# ESP8266.net
KiCad netlist of a schematic drawn in EAGLE
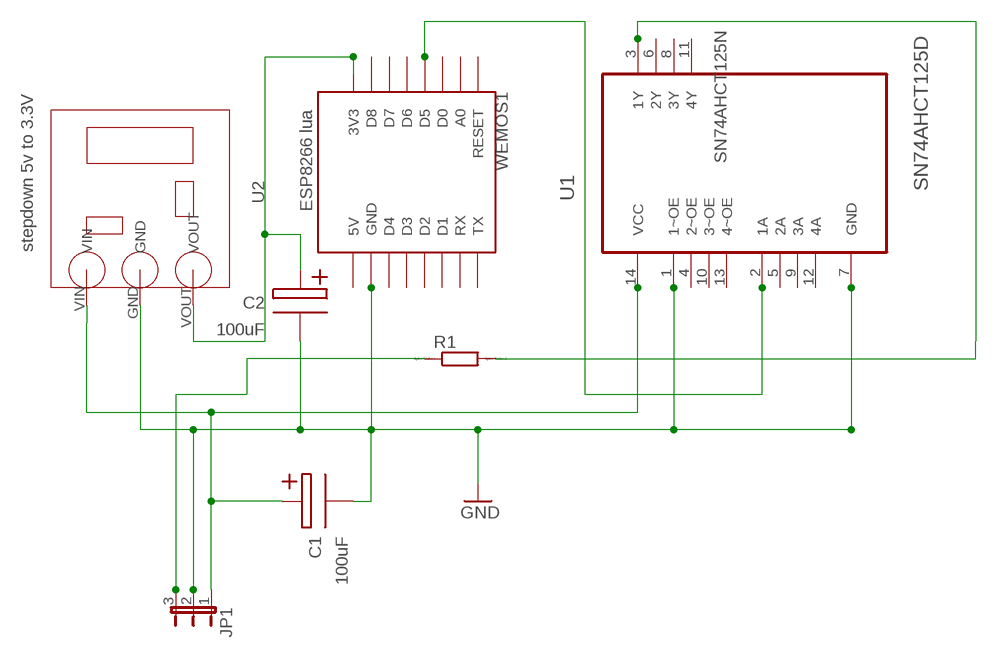
[diagram p0: schematic, sheet 1]

(export (version "E")
  (design (tool "Eeschema 10.0.6"))
  (components
    (comp (ref "C1")
      (value "100uF")
      (footprint "eagle-import:GEPOLTER_ELEKTROLYTKONDENSATOR")
      (libsource (lib "eagle-import") (part "GEPOLTER_ELEKTROLYTKONDENSATOR"))
    )
    (comp (ref "C2")
      (value "100uF")
      (footprint "eagle-import:GEPOLTER_ELEKTROLYTKONDENSATOR")
      (libsource (lib "eagle-import") (part "GEPOLTER_ELEKTROLYTKONDENSATOR"))
    )
    (comp (ref "JP1")
      (value "JP2W")
      (footprint "eagle-import:JP2W")
      (libsource (lib "eagle-import") (part "JP2W"))
    )
    (comp (ref "R1")
      (value "R0204/7")
      (footprint "eagle-import:0204_7")
      (libsource (lib "eagle-import") (part "R0204/7"))
    )
    (comp (ref "U1")
      (value "SN74AHCT125D")
      (footprint "eagle-import:SOIC127P600X175-14N")
      (fields (field (name "MPN") "SN74AHCT125D") (field (name "MPN_1") "SN74AHCT125N"))
      (libsource (lib "eagle-import") (part "SN74AHCT125D"))
    )
    (comp (ref "U2")
      (value "stepdown 5v to 3.3V")
      (footprint "eagle-import:STEPDOWN")
      (libsource (lib "eagle-import") (part "STEPDOWN"))
    )
    (comp (ref "WEMOS1")
      (value "ESP8266 lua")
      (footprint "eagle-import:WEMOS-D1-MINI")
      (libsource (lib "eagle-import") (part "WEMOS-D1-MINI"))
    )
  )
  (nets
    (net (code "1") (name "GND") (class "Default")
      (node (ref "C1") (pin "-") (pinfunction "-_-") (pintype "passive"))
      (node (ref "C2") (pin "-") (pinfunction "-_-") (pintype "passive"))
      (node (ref "JP1") (pin "2") (pinfunction "2_2") (pintype "passive"))
      (node (ref "U1") (pin "1") (pinfunction "1~{OE}_1") (pintype "input"))
      (node (ref "U1") (pin "7") (pinfunction "GND_7") (pintype "passive"))
      (node (ref "U2") (pin "GND") (pinfunction "GND_GND") (pintype "power_in"))
      (node (ref "WEMOS1") (pin "GND") (pinfunction "GND_GND") (pintype "bidirectional"))
    )
    (net (code "2") (name "Net-(C2-Pad+)") (class "Default")
      (node (ref "C2") (pin "+") (pinfunction "+_+") (pintype "passive"))
      (node (ref "U2") (pin "VOUT") (pinfunction "VOUT_VOUT") (pintype "power_in"))
      (node (ref "WEMOS1") (pin "3V3") (pinfunction "3V3_3V3") (pintype "bidirectional"))
    )
    (net (code "3") (name "Net-(JP1-Pad3)") (class "Default")
      (node (ref "JP1") (pin "3") (pinfunction "3_3") (pintype "passive"))
      (node (ref "R1") (pin "1") (pinfunction "1_1") (pintype "passive"))
    )
    (net (code "4") (name "Net-(U1-1A)") (class "Default")
      (node (ref "U1") (pin "2") (pinfunction "1A_2") (pintype "input"))
      (node (ref "WEMOS1") (pin "D5") (pinfunction "D5_D5") (pintype "bidirectional"))
    )
    (net (code "5") (name "Net-(U1-1Y)") (class "Default")
      (node (ref "R1") (pin "2") (pinfunction "2_2") (pintype "passive"))
      (node (ref "U1") (pin "3") (pinfunction "1Y_3") (pintype "output"))
    )
    (net (code "6") (name "Net-(U1-VCC)") (class "Default")
      (node (ref "C1") (pin "+") (pinfunction "+_+") (pintype "passive"))
      (node (ref "JP1") (pin "1") (pinfunction "1_1") (pintype "passive"))
      (node (ref "U1") (pin "14") (pinfunction "VCC_14") (pintype "power_in"))
      (node (ref "U2") (pin "VIN") (pinfunction "VIN_VIN") (pintype "power_in"))
    )
    (net (code "7") (name "unconnected-(U1-2A-Pad5)") (class "Default")
      (node (ref "U1") (pin "5") (pinfunction "2A_5") (pintype "input"))
    )
    (net (code "8") (name "unconnected-(U1-2Y-Pad6)") (class "Default")
      (node (ref "U1") (pin "6") (pinfunction "2Y_6") (pintype "output"))
    )
    (net (code "9") (name "unconnected-(U1-2~{OE}-Pad4)") (class "Default")
      (node (ref "U1") (pin "4") (pinfunction "2~{OE}_4") (pintype "input"))
    )
    (net (code "10") (name "unconnected-(U1-3A-Pad9)") (class "Default")
      (node (ref "U1") (pin "9") (pinfunction "3A_9") (pintype "input"))
    )
    (net (code "11") (name "unconnected-(U1-3Y-Pad8)") (class "Default")
      (node (ref "U1") (pin "8") (pinfunction "3Y_8") (pintype "output"))
    )
    (net (code "12") (name "unconnected-(U1-3~{OE}-Pad10)") (class "Default")
      (node (ref "U1") (pin "10") (pinfunction "3~{OE}_10") (pintype "input"))
    )
    (net (code "13") (name "unconnected-(U1-4A-Pad12)") (class "Default")
      (node (ref "U1") (pin "12") (pinfunction "4A_12") (pintype "input"))
    )
    (net (code "14") (name "unconnected-(U1-4Y-Pad11)") (class "Default")
      (node (ref "U1") (pin "11") (pinfunction "4Y_11") (pintype "output"))
    )
    (net (code "15") (name "unconnected-(U1-4~{OE}-Pad13)") (class "Default")
      (node (ref "U1") (pin "13") (pinfunction "4~{OE}_13") (pintype "input"))
    )
    (net (code "16") (name "unconnected-(WEMOS1-Pad5V)") (class "Default")
      (node (ref "WEMOS1") (pin "5V") (pinfunction "5V_5V") (pintype "bidirectional"))
    )
    (net (code "17") (name "unconnected-(WEMOS1-PadA0)") (class "Default")
      (node (ref "WEMOS1") (pin "A0") (pinfunction "A0_A0") (pintype "bidirectional"))
    )
    (net (code "18") (name "unconnected-(WEMOS1-PadD0)") (class "Default")
      (node (ref "WEMOS1") (pin "D0") (pinfunction "D0_D0") (pintype "bidirectional"))
    )
    (net (code "19") (name "unconnected-(WEMOS1-PadD1)") (class "Default")
      (node (ref "WEMOS1") (pin "D1") (pinfunction "D1_D1") (pintype "bidirectional"))
    )
    (net (code "20") (name "unconnected-(WEMOS1-PadD2)") (class "Default")
      (node (ref "WEMOS1") (pin "D2") (pinfunction "D2_D2") (pintype "bidirectional"))
    )
    (net (code "21") (name "unconnected-(WEMOS1-PadD3)") (class "Default")
      (node (ref "WEMOS1") (pin "D3") (pinfunction "D3_D3") (pintype "bidirectional"))
    )
    (net (code "22") (name "unconnected-(WEMOS1-PadD4)") (class "Default")
      (node (ref "WEMOS1") (pin "D4") (pinfunction "D4_D4") (pintype "bidirectional"))
    )
    (net (code "23") (name "unconnected-(WEMOS1-PadD6)") (class "Default")
      (node (ref "WEMOS1") (pin "D6") (pinfunction "D6_D6") (pintype "bidirectional"))
    )
    (net (code "24") (name "unconnected-(WEMOS1-PadD7)") (class "Default")
      (node (ref "WEMOS1") (pin "D7") (pinfunction "D7_D7") (pintype "bidirectional"))
    )
    (net (code "25") (name "unconnected-(WEMOS1-PadD8)") (class "Default")
      (node (ref "WEMOS1") (pin "D8") (pinfunction "D8_D8") (pintype "bidirectional"))
    )
    (net (code "26") (name "unconnected-(WEMOS1-PadRESET)") (class "Default")
      (node (ref "WEMOS1") (pin "RESET") (pinfunction "RESET_RESET") (pintype "bidirectional"))
    )
    (net (code "27") (name "unconnected-(WEMOS1-PadRX)") (class "Default")
      (node (ref "WEMOS1") (pin "RX") (pinfunction "RX_RX") (pintype "bidirectional"))
    )
    (net (code "28") (name "unconnected-(WEMOS1-PadTX)") (class "Default")
      (node (ref "WEMOS1") (pin "TX") (pinfunction "TX_TX") (pintype "bidirectional"))
    )
  )
)
